# versao4_0.net
KiCad netlist of a schematic drawn in EAGLE
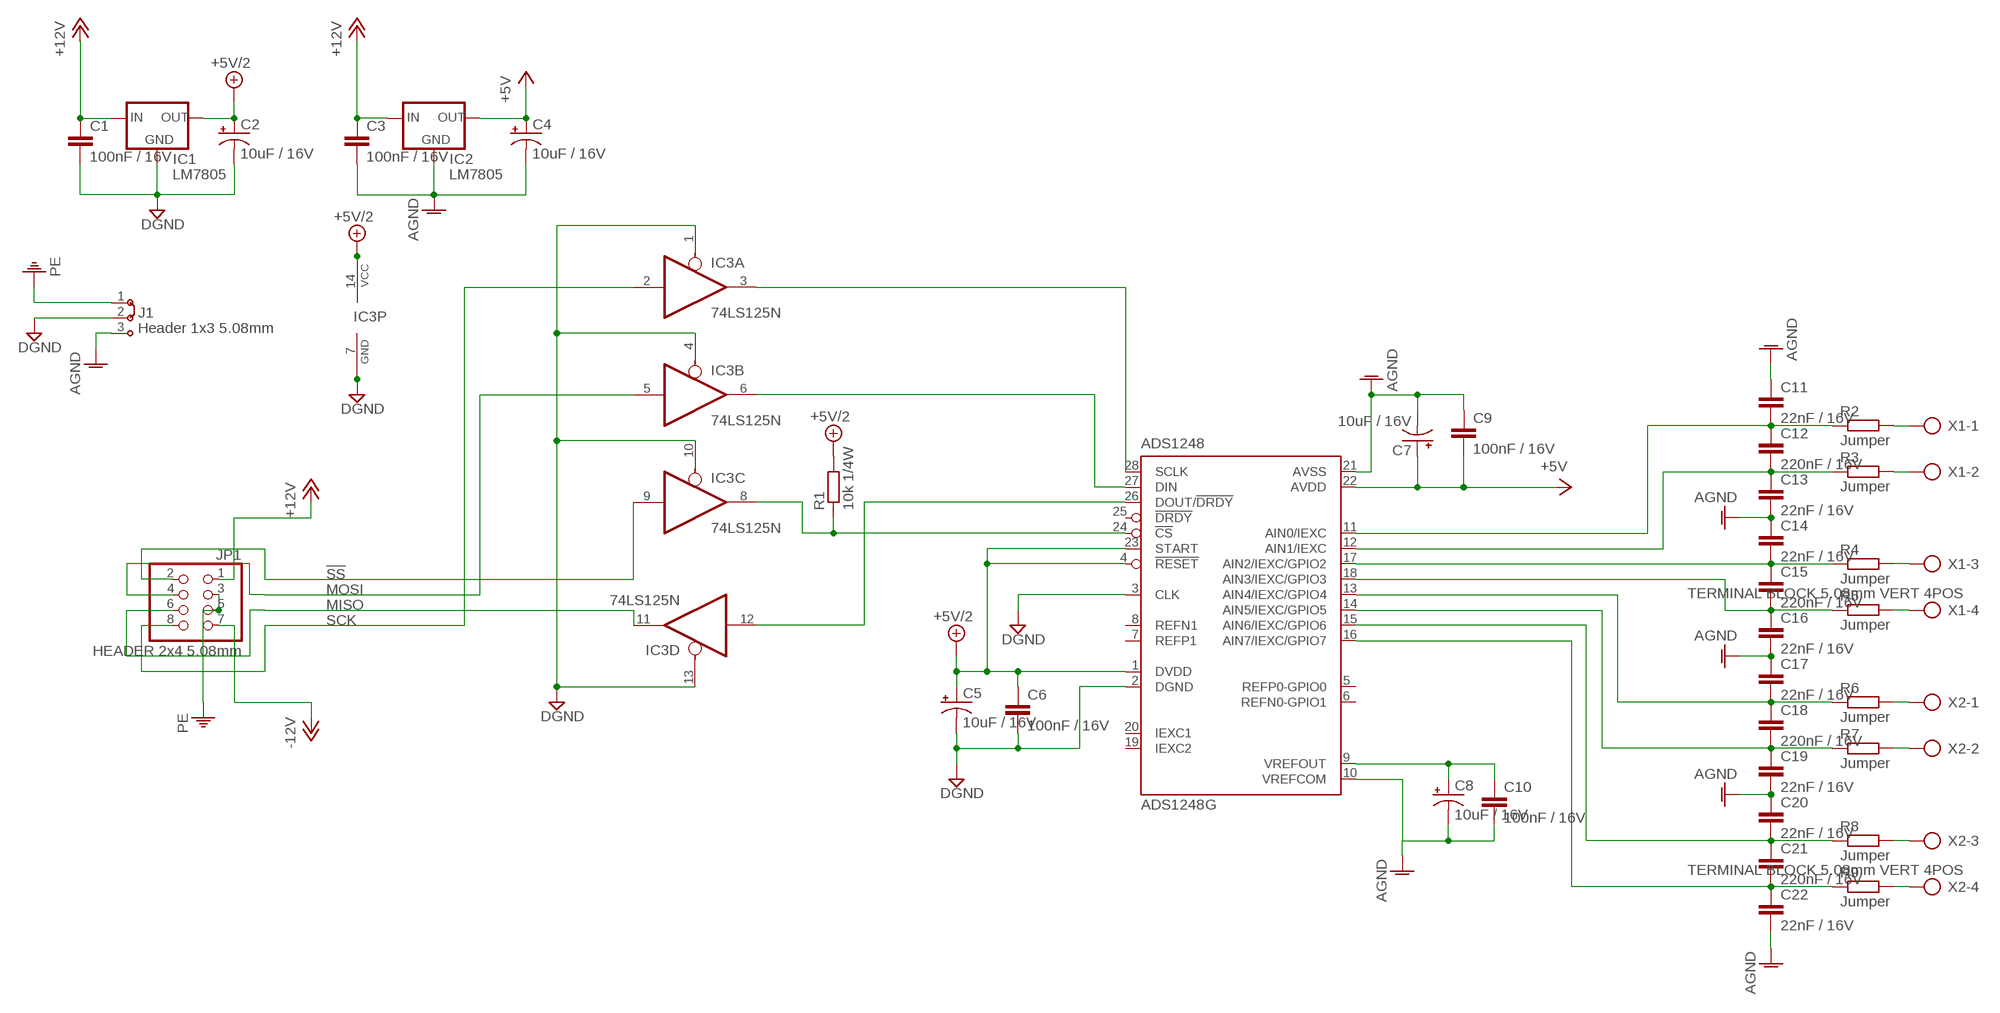
[diagram p0: schematic, sheet 1]

(export (version "E")
  (design (tool "Eeschema 10.0.6"))
  (components
    (comp (ref "C1")
      (value "100nF / 16V")
      (footprint "eagle-import:C5B3")
      (libsource (lib "eagle-import") (part "C5/3"))
    )
    (comp (ref "C2")
      (value "10uF / 16V")
      (footprint "eagle-import:E2-5")
      (libsource (lib "eagle-import") (part "CPOL-USE2-5"))
    )
    (comp (ref "C3")
      (value "100nF / 16V")
      (footprint "eagle-import:C5B3")
      (libsource (lib "eagle-import") (part "C5/3"))
    )
    (comp (ref "C4")
      (value "10uF / 16V")
      (footprint "eagle-import:E2-5")
      (libsource (lib "eagle-import") (part "CPOL-USE2-5"))
    )
    (comp (ref "C5")
      (value "10uF / 16V")
      (footprint "eagle-import:E2-5")
      (libsource (lib "eagle-import") (part "CPOL-USE2-5"))
    )
    (comp (ref "C6")
      (value "100nF / 16V")
      (footprint "eagle-import:C5B3")
      (libsource (lib "eagle-import") (part "C5/3"))
    )
    (comp (ref "C7")
      (value "10uF / 16V")
      (footprint "eagle-import:E2-5")
      (libsource (lib "eagle-import") (part "CPOL-USE2-5"))
    )
    (comp (ref "C8")
      (value "10uF / 16V")
      (footprint "eagle-import:E2-5")
      (libsource (lib "eagle-import") (part "CPOL-USE2-5"))
    )
    (comp (ref "C9")
      (value "100nF / 16V")
      (footprint "eagle-import:C5B3")
      (libsource (lib "eagle-import") (part "C5/3"))
    )
    (comp (ref "C10")
      (value "100nF / 16V")
      (footprint "eagle-import:C5B3")
      (libsource (lib "eagle-import") (part "C5/3"))
    )
    (comp (ref "C11")
      (value "22nF / 16V")
      (footprint "eagle-import:C5B2.5")
      (libsource (lib "eagle-import") (part "C5/2.5"))
    )
    (comp (ref "C12")
      (value "220nF / 16V")
      (footprint "eagle-import:C5B2.5")
      (libsource (lib "eagle-import") (part "C5/2.5"))
    )
    (comp (ref "C13")
      (value "22nF / 16V")
      (footprint "eagle-import:C5B2.5")
      (libsource (lib "eagle-import") (part "C5/2.5"))
    )
    (comp (ref "C14")
      (value "22nF / 16V")
      (footprint "eagle-import:C5B2.5")
      (libsource (lib "eagle-import") (part "C5/2.5"))
    )
    (comp (ref "C15")
      (value "220nF / 16V")
      (footprint "eagle-import:C5B2.5")
      (libsource (lib "eagle-import") (part "C5/2.5"))
    )
    (comp (ref "C16")
      (value "22nF / 16V")
      (footprint "eagle-import:C5B2.5")
      (libsource (lib "eagle-import") (part "C5/2.5"))
    )
    (comp (ref "C17")
      (value "22nF / 16V")
      (footprint "eagle-import:C5B2.5")
      (libsource (lib "eagle-import") (part "C5/2.5"))
    )
    (comp (ref "C18")
      (value "220nF / 16V")
      (footprint "eagle-import:C5B2.5")
      (libsource (lib "eagle-import") (part "C5/2.5"))
    )
    (comp (ref "C19")
      (value "22nF / 16V")
      (footprint "eagle-import:C5B3")
      (libsource (lib "eagle-import") (part "C5/3"))
    )
    (comp (ref "C20")
      (value "22nF / 16V")
      (footprint "eagle-import:C5B2.5")
      (libsource (lib "eagle-import") (part "C5/2.5"))
    )
    (comp (ref "C21")
      (value "220nF / 16V")
      (footprint "eagle-import:C5B2.5")
      (libsource (lib "eagle-import") (part "C5/2.5"))
    )
    (comp (ref "C22")
      (value "22nF / 16V")
      (footprint "eagle-import:C5B2.5")
      (libsource (lib "eagle-import") (part "C5/2.5"))
    )
    (comp (ref "IC1")
      (value "LM7805")
      (footprint "eagle-import:78XXL")
      (libsource (lib "eagle-import") (part "78XXL"))
    )
    (comp (ref "IC2")
      (value "LM7805")
      (footprint "eagle-import:78XXL")
      (libsource (lib "eagle-import") (part "78XXL"))
    )
    (comp (ref "IC3")
      (value "74LS125N")
      (footprint "eagle-import:DIL14")
      (libsource (lib "eagle-import") (part "74125NLS"))
    )
    (comp (ref "IC4")
      (value "ADS1248G")
      (footprint "eagle-import:P-TSSOP28-1")
      (libsource (lib "eagle-import") (part "ADS1248G"))
    )
    (comp (ref "J1")
      (value "Header 1x3 5.08mm")
      (footprint "eagle-import:04C")
      (libsource (lib "eagle-import") (part "J2X2MM"))
    )
    (comp (ref "JP1")
      (value "HEADER 2x4 5.08mm")
      (footprint "eagle-import:2X04")
      (libsource (lib "eagle-import") (part "PINHD-2X4"))
    )
    (comp (ref "R1")
      (value "10k 1/4W")
      (footprint "eagle-import:0204_7")
      (libsource (lib "eagle-import") (part "R-EU_0204/7"))
    )
    (comp (ref "R2")
      (value "Jumper")
      (footprint "eagle-import:0204_7")
      (libsource (lib "eagle-import") (part "R-EU_0204/7"))
    )
    (comp (ref "R3")
      (value "Jumper")
      (footprint "eagle-import:0204_7")
      (libsource (lib "eagle-import") (part "R-EU_0204/7"))
    )
    (comp (ref "R4")
      (value "Jumper")
      (footprint "eagle-import:0204_7")
      (libsource (lib "eagle-import") (part "R-EU_0204/7"))
    )
    (comp (ref "R5")
      (value "Jumper")
      (footprint "eagle-import:0204_7")
      (libsource (lib "eagle-import") (part "R-EU_0204/7"))
    )
    (comp (ref "R6")
      (value "Jumper")
      (footprint "eagle-import:0204_7")
      (libsource (lib "eagle-import") (part "R-EU_0204/7"))
    )
    (comp (ref "R7")
      (value "Jumper")
      (footprint "eagle-import:0204_7")
      (libsource (lib "eagle-import") (part "R-EU_0204/7"))
    )
    (comp (ref "R8")
      (value "Jumper")
      (footprint "eagle-import:0204_7")
      (libsource (lib "eagle-import") (part "R-EU_0204/7"))
    )
    (comp (ref "R9")
      (value "Jumper")
      (footprint "eagle-import:0204_7")
      (libsource (lib "eagle-import") (part "R-EU_0204/7"))
    )
    (comp (ref "X1")
      (value "TERMINAL BLOCK 5.08mm VERT 4POS")
      (footprint "eagle-import:AK500_4-H")
      (libsource (lib "eagle-import") (part "AK500/4-H"))
    )
    (comp (ref "X2")
      (value "TERMINAL BLOCK 5.08mm VERT 4POS")
      (footprint "eagle-import:AK500_4-H")
      (libsource (lib "eagle-import") (part "AK500/4-H"))
    )
  )
  (nets
    (net (code "1") (name "+5V") (class "Default")
      (node (ref "C4") (pin "+") (pinfunction "+_+") (pintype "passive"))
      (node (ref "C7") (pin "+") (pinfunction "+_+") (pintype "passive"))
      (node (ref "C9") (pin "2") (pinfunction "2_2") (pintype "passive"))
      (node (ref "IC2") (pin "OUT") (pinfunction "OUT_OUT") (pintype "passive"))
      (node (ref "IC4") (pin "22") (pinfunction "AVDD_22") (pintype "input"))
    )
    (net (code "2") (name "+5V{slash}2") (class "Default")
      (node (ref "C2") (pin "+") (pinfunction "+_+") (pintype "passive"))
      (node (ref "C5") (pin "+") (pinfunction "+_+") (pintype "passive"))
      (node (ref "C6") (pin "1") (pinfunction "1_1") (pintype "passive"))
      (node (ref "IC1") (pin "OUT") (pinfunction "OUT_OUT") (pintype "passive"))
      (node (ref "IC3") (pin "14") (pinfunction "VCC_14") (pintype "power_in"))
      (node (ref "IC4") (pin "1") (pinfunction "DVDD_1") (pintype "input"))
      (node (ref "IC4") (pin "23") (pinfunction "START_23") (pintype "input"))
      (node (ref "IC4") (pin "4") (pinfunction "~{RESET}_4") (pintype "input"))
      (node (ref "R1") (pin "2") (pinfunction "2_2") (pintype "passive"))
    )
    (net (code "3") (name "+12V") (class "Default")
      (node (ref "C1") (pin "1") (pinfunction "1_1") (pintype "passive"))
      (node (ref "C3") (pin "1") (pinfunction "1_1") (pintype "passive"))
      (node (ref "IC1") (pin "IN") (pinfunction "IN_IN") (pintype "input"))
      (node (ref "IC2") (pin "IN") (pinfunction "IN_IN") (pintype "input"))
      (node (ref "JP1") (pin "1") (pinfunction "1_1") (pintype "passive"))
    )
    (net (code "4") (name "-12V") (class "Default")
      (node (ref "JP1") (pin "7") (pinfunction "7_7") (pintype "passive"))
    )
    (net (code "5") (name "/MISO") (class "Default")
      (node (ref "IC3") (pin "11") (pinfunction "O_11") (pintype "tri_state"))
      (node (ref "JP1") (pin "6") (pinfunction "6_6") (pintype "passive"))
    )
    (net (code "6") (name "/MOSI") (class "Default")
      (node (ref "IC3") (pin "5") (pinfunction "I_5") (pintype "input"))
      (node (ref "JP1") (pin "4") (pinfunction "4_4") (pintype "passive"))
    )
    (net (code "7") (name "/SCK") (class "Default")
      (node (ref "IC3") (pin "2") (pinfunction "I_2") (pintype "input"))
      (node (ref "JP1") (pin "8") (pinfunction "8_8") (pintype "passive"))
    )
    (net (code "8") (name "/~{SS}") (class "Default")
      (node (ref "IC3") (pin "9") (pinfunction "I_9") (pintype "input"))
      (node (ref "JP1") (pin "2") (pinfunction "2_2") (pintype "passive"))
    )
    (net (code "9") (name "AGND") (class "Default")
      (node (ref "C10") (pin "2") (pinfunction "2_2") (pintype "passive"))
      (node (ref "C11") (pin "1") (pinfunction "1_1") (pintype "passive"))
      (node (ref "C13") (pin "2") (pinfunction "2_2") (pintype "passive"))
      (node (ref "C14") (pin "1") (pinfunction "1_1") (pintype "passive"))
      (node (ref "C16") (pin "2") (pinfunction "2_2") (pintype "passive"))
      (node (ref "C17") (pin "1") (pinfunction "1_1") (pintype "passive"))
      (node (ref "C19") (pin "2") (pinfunction "2_2") (pintype "passive"))
      (node (ref "C20") (pin "1") (pinfunction "1_1") (pintype "passive"))
      (node (ref "C22") (pin "2") (pinfunction "2_2") (pintype "passive"))
      (node (ref "C3") (pin "2") (pinfunction "2_2") (pintype "passive"))
      (node (ref "C4") (pin "-") (pinfunction "-_-") (pintype "passive"))
      (node (ref "C7") (pin "-") (pinfunction "-_-") (pintype "passive"))
      (node (ref "C8") (pin "-") (pinfunction "-_-") (pintype "passive"))
      (node (ref "C9") (pin "1") (pinfunction "1_1") (pintype "passive"))
      (node (ref "IC2") (pin "GND") (pinfunction "GND_GND") (pintype "input"))
      (node (ref "IC4") (pin "10") (pinfunction "VREFCOM_10") (pintype "output"))
      (node (ref "IC4") (pin "21") (pinfunction "AVSS_21") (pintype "input"))
      (node (ref "J1") (pin "3") (pinfunction "3_3") (pintype "passive"))
    )
    (net (code "10") (name "DGND") (class "Default")
      (node (ref "C1") (pin "2") (pinfunction "2_2") (pintype "passive"))
      (node (ref "C2") (pin "-") (pinfunction "-_-") (pintype "passive"))
      (node (ref "C5") (pin "-") (pinfunction "-_-") (pintype "passive"))
      (node (ref "C6") (pin "2") (pinfunction "2_2") (pintype "passive"))
      (node (ref "IC1") (pin "GND") (pinfunction "GND_GND") (pintype "input"))
      (node (ref "IC3") (pin "1") (pinfunction "OE_1") (pintype "input"))
      (node (ref "IC3") (pin "10") (pinfunction "OE_10") (pintype "input"))
      (node (ref "IC3") (pin "13") (pinfunction "OE_13") (pintype "input"))
      (node (ref "IC3") (pin "4") (pinfunction "OE_4") (pintype "input"))
      (node (ref "IC3") (pin "7") (pinfunction "GND_7") (pintype "power_in"))
      (node (ref "IC4") (pin "2") (pinfunction "DGND_2") (pintype "input"))
      (node (ref "IC4") (pin "3") (pinfunction "CLK_3") (pintype "input"))
      (node (ref "J1") (pin "2") (pinfunction "2_2") (pintype "passive"))
    )
    (net (code "11") (name "Net-(IC3A-O)") (class "Default")
      (node (ref "IC3") (pin "3") (pinfunction "O_3") (pintype "tri_state"))
      (node (ref "IC4") (pin "28") (pinfunction "SCLK_28") (pintype "input"))
    )
    (net (code "12") (name "Net-(IC3B-O)") (class "Default")
      (node (ref "IC3") (pin "6") (pinfunction "O_6") (pintype "tri_state"))
      (node (ref "IC4") (pin "27") (pinfunction "DIN_27") (pintype "input"))
    )
    (net (code "13") (name "Net-(IC3C-O)") (class "Default")
      (node (ref "IC3") (pin "8") (pinfunction "O_8") (pintype "tri_state"))
      (node (ref "IC4") (pin "24") (pinfunction "~{CS}_24") (pintype "input"))
      (node (ref "R1") (pin "1") (pinfunction "1_1") (pintype "passive"))
    )
    (net (code "14") (name "Net-(IC3D-I)") (class "Default")
      (node (ref "IC3") (pin "12") (pinfunction "I_12") (pintype "input"))
      (node (ref "IC4") (pin "26") (pinfunction "DOUT/~{DRDY}_26") (pintype "output"))
    )
    (net (code "15") (name "Net-(IC4-AIN0{slash}IEXC)") (class "Default")
      (node (ref "C11") (pin "2") (pinfunction "2_2") (pintype "passive"))
      (node (ref "C12") (pin "1") (pinfunction "1_1") (pintype "passive"))
      (node (ref "IC4") (pin "11") (pinfunction "AIN0/IEXC_11") (pintype "bidirectional"))
      (node (ref "R2") (pin "1") (pinfunction "1_1") (pintype "passive"))
    )
    (net (code "16") (name "Net-(IC4-AIN1{slash}IEXC)") (class "Default")
      (node (ref "C12") (pin "2") (pinfunction "2_2") (pintype "passive"))
      (node (ref "C13") (pin "1") (pinfunction "1_1") (pintype "passive"))
      (node (ref "IC4") (pin "12") (pinfunction "AIN1/IEXC_12") (pintype "bidirectional"))
      (node (ref "R3") (pin "1") (pinfunction "1_1") (pintype "passive"))
    )
    (net (code "17") (name "Net-(IC4-AIN2{slash}IEXC{slash}GPIO2)") (class "Default")
      (node (ref "C14") (pin "2") (pinfunction "2_2") (pintype "passive"))
      (node (ref "C15") (pin "1") (pinfunction "1_1") (pintype "passive"))
      (node (ref "IC4") (pin "17") (pinfunction "AIN2/IEXC/GPIO2_17") (pintype "bidirectional"))
      (node (ref "R4") (pin "1") (pinfunction "1_1") (pintype "passive"))
    )
    (net (code "18") (name "Net-(IC4-AIN3{slash}IEXC{slash}GPIO3)") (class "Default")
      (node (ref "C15") (pin "2") (pinfunction "2_2") (pintype "passive"))
      (node (ref "C16") (pin "1") (pinfunction "1_1") (pintype "passive"))
      (node (ref "IC4") (pin "18") (pinfunction "AIN3/IEXC/GPIO3_18") (pintype "bidirectional"))
      (node (ref "R5") (pin "1") (pinfunction "1_1") (pintype "passive"))
    )
    (net (code "19") (name "Net-(IC4-AIN4{slash}IEXC{slash}GPIO4)") (class "Default")
      (node (ref "C17") (pin "2") (pinfunction "2_2") (pintype "passive"))
      (node (ref "C18") (pin "1") (pinfunction "1_1") (pintype "passive"))
      (node (ref "IC4") (pin "13") (pinfunction "AIN4/IEXC/GPIO4_13") (pintype "bidirectional"))
      (node (ref "R6") (pin "1") (pinfunction "1_1") (pintype "passive"))
    )
    (net (code "20") (name "Net-(IC4-AIN5{slash}IEXC{slash}GPIO5)") (class "Default")
      (node (ref "C18") (pin "2") (pinfunction "2_2") (pintype "passive"))
      (node (ref "C19") (pin "1") (pinfunction "1_1") (pintype "passive"))
      (node (ref "IC4") (pin "14") (pinfunction "AIN5/IEXC/GPIO5_14") (pintype "bidirectional"))
      (node (ref "R7") (pin "1") (pinfunction "1_1") (pintype "passive"))
    )
    (net (code "21") (name "Net-(IC4-AIN6{slash}IEXC{slash}GPIO6)") (class "Default")
      (node (ref "C20") (pin "2") (pinfunction "2_2") (pintype "passive"))
      (node (ref "C21") (pin "1") (pinfunction "1_1") (pintype "passive"))
      (node (ref "IC4") (pin "15") (pinfunction "AIN6/IEXC/GPIO6_15") (pintype "bidirectional"))
      (node (ref "R8") (pin "1") (pinfunction "1_1") (pintype "passive"))
    )
    (net (code "22") (name "Net-(IC4-AIN7{slash}IEXC{slash}GPIO7)") (class "Default")
      (node (ref "C21") (pin "2") (pinfunction "2_2") (pintype "passive"))
      (node (ref "C22") (pin "1") (pinfunction "1_1") (pintype "passive"))
      (node (ref "IC4") (pin "16") (pinfunction "AIN7/IEXC/GPIO7_16") (pintype "bidirectional"))
      (node (ref "R9") (pin "1") (pinfunction "1_1") (pintype "passive"))
    )
    (net (code "23") (name "Net-(IC4-VREFOUT)") (class "Default")
      (node (ref "C10") (pin "1") (pinfunction "1_1") (pintype "passive"))
      (node (ref "C8") (pin "+") (pinfunction "+_+") (pintype "passive"))
      (node (ref "IC4") (pin "9") (pinfunction "VREFOUT_9") (pintype "output"))
    )
    (net (code "24") (name "Net-(X1A-KL)") (class "Default")
      (node (ref "R2") (pin "2") (pinfunction "2_2") (pintype "passive"))
      (node (ref "X1") (pin "1") (pinfunction "KL_1") (pintype "passive"))
    )
    (net (code "25") (name "Net-(X1B-KL)") (class "Default")
      (node (ref "R3") (pin "2") (pinfunction "2_2") (pintype "passive"))
      (node (ref "X1") (pin "2") (pinfunction "KL_2") (pintype "passive"))
    )
    (net (code "26") (name "Net-(X1C-KL)") (class "Default")
      (node (ref "R4") (pin "2") (pinfunction "2_2") (pintype "passive"))
      (node (ref "X1") (pin "3") (pinfunction "KL_3") (pintype "passive"))
    )
    (net (code "27") (name "Net-(X1D-KL)") (class "Default")
      (node (ref "R5") (pin "2") (pinfunction "2_2") (pintype "passive"))
      (node (ref "X1") (pin "4") (pinfunction "KL_4") (pintype "passive"))
    )
    (net (code "28") (name "Net-(X2A-KL)") (class "Default")
      (node (ref "R6") (pin "2") (pinfunction "2_2") (pintype "passive"))
      (node (ref "X2") (pin "1") (pinfunction "KL_1") (pintype "passive"))
    )
    (net (code "29") (name "Net-(X2B-KL)") (class "Default")
      (node (ref "R7") (pin "2") (pinfunction "2_2") (pintype "passive"))
      (node (ref "X2") (pin "2") (pinfunction "KL_2") (pintype "passive"))
    )
    (net (code "30") (name "Net-(X2C-KL)") (class "Default")
      (node (ref "R8") (pin "2") (pinfunction "2_2") (pintype "passive"))
      (node (ref "X2") (pin "3") (pinfunction "KL_3") (pintype "passive"))
    )
    (net (code "31") (name "Net-(X2D-KL)") (class "Default")
      (node (ref "R9") (pin "2") (pinfunction "2_2") (pintype "passive"))
      (node (ref "X2") (pin "4") (pinfunction "KL_4") (pintype "passive"))
    )
    (net (code "32") (name "PE") (class "Default")
      (node (ref "J1") (pin "1") (pinfunction "1_1") (pintype "passive"))
      (node (ref "JP1") (pin "3") (pinfunction "3_3") (pintype "passive"))
      (node (ref "JP1") (pin "5") (pinfunction "5_5") (pintype "passive"))
    )
    (net (code "33") (name "unconnected-(IC4-IEXC1-Pad20)") (class "Default")
      (node (ref "IC4") (pin "20") (pinfunction "IEXC1_20") (pintype "output"))
    )
    (net (code "34") (name "unconnected-(IC4-IEXC2-Pad19)") (class "Default")
      (node (ref "IC4") (pin "19") (pinfunction "IEXC2_19") (pintype "output"))
    )
    (net (code "35") (name "unconnected-(IC4-REFN0-GPIO1-Pad6)") (class "Default")
      (node (ref "IC4") (pin "6") (pinfunction "REFN0-GPIO1_6") (pintype "bidirectional"))
    )
    (net (code "36") (name "unconnected-(IC4-REFN1-Pad8)") (class "Default")
      (node (ref "IC4") (pin "8") (pinfunction "REFN1_8") (pintype "bidirectional"))
    )
    (net (code "37") (name "unconnected-(IC4-REFP0-GPIO0-Pad5)") (class "Default")
      (node (ref "IC4") (pin "5") (pinfunction "REFP0-GPIO0_5") (pintype "bidirectional"))
    )
    (net (code "38") (name "unconnected-(IC4-REFP1-Pad7)") (class "Default")
      (node (ref "IC4") (pin "7") (pinfunction "REFP1_7") (pintype "bidirectional"))
    )
    (net (code "39") (name "unconnected-(IC4-~{DRDY}-Pad25)") (class "Default")
      (node (ref "IC4") (pin "25") (pinfunction "~{DRDY}_25") (pintype "output"))
    )
  )
)
